# Decoupling_caps.net
KiCad netlist of a schematic drawn in Altium Designer
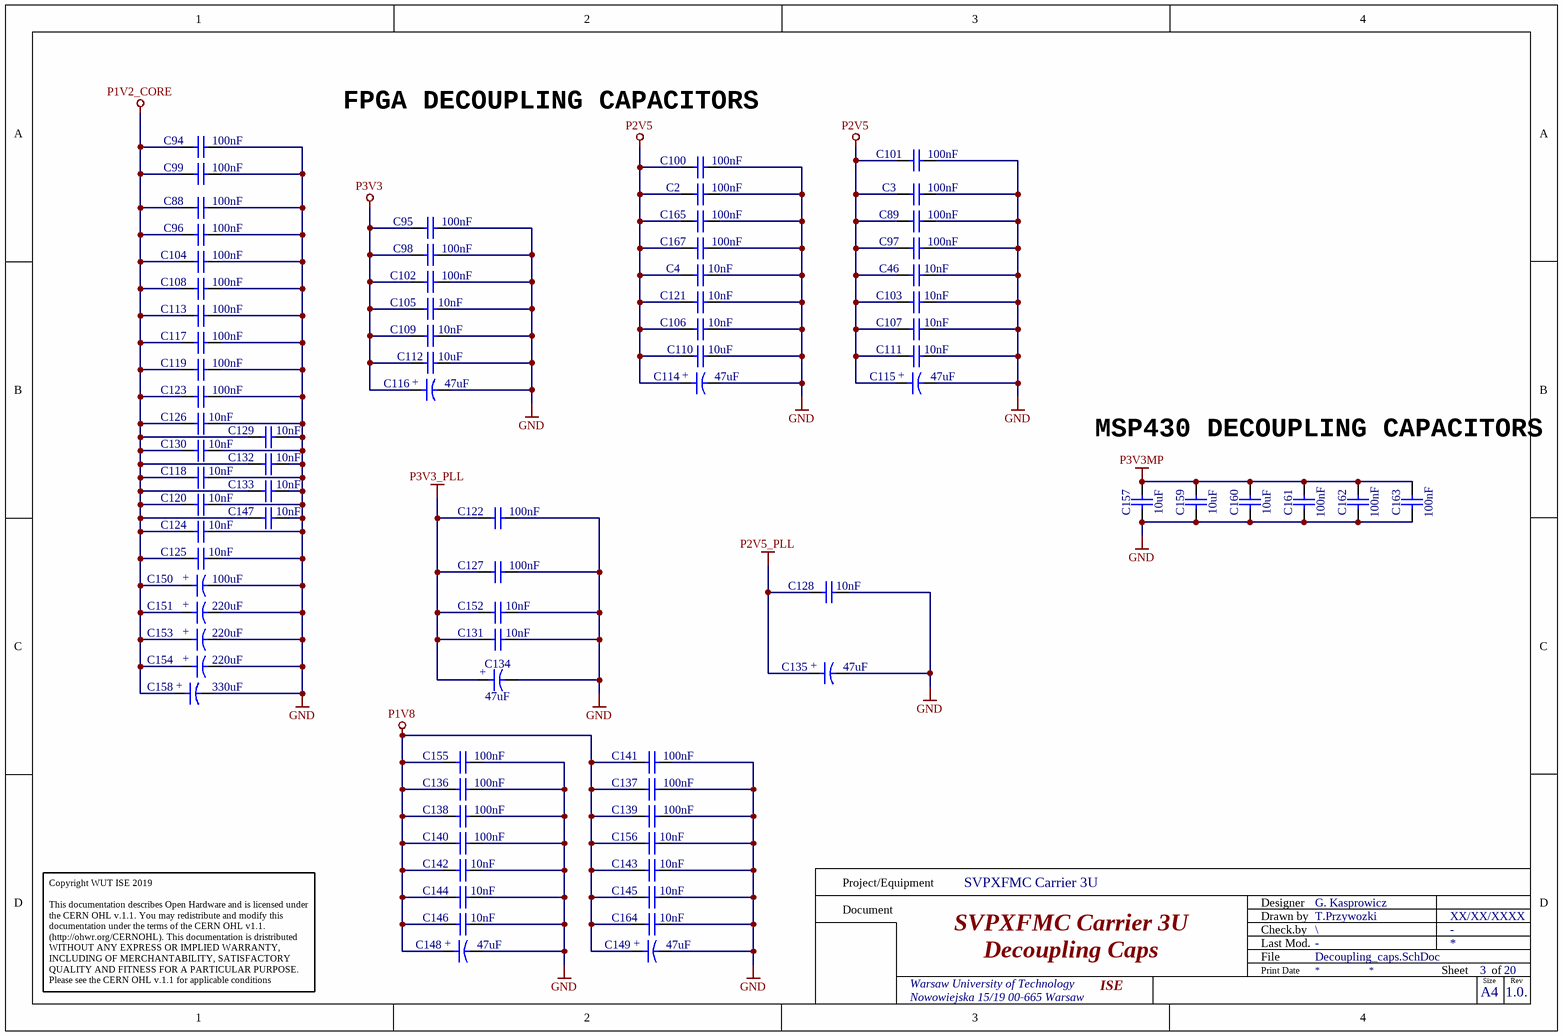
[diagram p0: Decoupling_caps.SchDoc]

(export (version "E")
  (design (tool "Eeschema 10.0.6"))
  (components
    (comp (ref "C2")
      (value "100nF")
      (footprint "CAPC0603X33N")
      (description "Non-polarised capacitor")
      (fields
        (field (name "MANUFACTURER") "GENERIC")
        (field (name "PART NUMBER") "CC0201_100NF_6.3V_10%_X5R")
        (field (name "AUTHOR") "CERN DEM JLC")
      )
      (libsource (lib "Capacitors") (part "Capacitor - non polarized"))
    )
    (comp (ref "C3")
      (value "100nF")
      (footprint "CAPC0603X33N")
      (description "Non-polarised capacitor")
      (fields
        (field (name "MANUFACTURER") "GENERIC")
        (field (name "PART NUMBER") "CC0201_100NF_6.3V_10%_X5R")
        (field (name "AUTHOR") "CERN DEM JLC")
      )
      (libsource (lib "Capacitors") (part "Capacitor - non polarized"))
    )
    (comp (ref "C4")
      (value "10nF")
      (footprint "CAPC0603X33N")
      (description "Non-polarised capacitor")
      (fields
        (field (name "MANUFACTURER") "GENERIC")
        (field (name "PART NUMBER") "CC0201_10NF_10V_10%_X5R")
        (field (name "AUTHOR") "CERN DEM JLC")
      )
      (libsource (lib "Capacitors") (part "Capacitor - non polarized"))
    )
    (comp (ref "C46")
      (value "10nF")
      (footprint "CAPC0603X33N")
      (description "Non-polarised capacitor")
      (fields
        (field (name "MANUFACTURER") "GENERIC")
        (field (name "PART NUMBER") "CC0201_10NF_10V_10%_X5R")
        (field (name "AUTHOR") "CERN DEM JLC")
      )
      (libsource (lib "Capacitors") (part "Capacitor - non polarized"))
    )
    (comp (ref "C88")
      (value "100nF")
      (footprint "CAPC0603X33N")
      (description "Non-polarised capacitor")
      (fields
        (field (name "MANUFACTURER") "GENERIC")
        (field (name "PART NUMBER") "CC0201_100NF_6.3V_10%_X5R")
        (field (name "AUTHOR") "CERN DEM JLC")
      )
      (libsource (lib "Capacitors") (part "Capacitor - non polarized"))
    )
    (comp (ref "C89")
      (value "100nF")
      (footprint "CAPC0603X33N")
      (description "Non-polarised capacitor")
      (fields
        (field (name "MANUFACTURER") "GENERIC")
        (field (name "PART NUMBER") "CC0201_100NF_6.3V_10%_X5R")
        (field (name "AUTHOR") "CERN DEM JLC")
      )
      (libsource (lib "Capacitors") (part "Capacitor - non polarized"))
    )
    (comp (ref "C94")
      (value "100nF")
      (footprint "CAPC0603X33N")
      (description "Non-polarised capacitor")
      (fields
        (field (name "MANUFACTURER") "GENERIC")
        (field (name "PART NUMBER") "CC0201_100NF_6.3V_10%_X5R")
        (field (name "AUTHOR") "CERN DEM JLC")
      )
      (libsource (lib "Capacitors") (part "Capacitor - non polarized"))
    )
    (comp (ref "C95")
      (value "100nF")
      (footprint "CAPC0603X33N")
      (description "Non-polarised capacitor")
      (fields
        (field (name "MANUFACTURER") "GENERIC")
        (field (name "PART NUMBER") "CC0201_100NF_6.3V_10%_X5R")
        (field (name "AUTHOR") "CERN DEM JLC")
      )
      (libsource (lib "Capacitors") (part "Capacitor - non polarized"))
    )
    (comp (ref "C96")
      (value "100nF")
      (footprint "CAPC0603X33N")
      (description "Non-polarised capacitor")
      (fields
        (field (name "MANUFACTURER") "GENERIC")
        (field (name "PART NUMBER") "CC0201_100NF_6.3V_10%_X5R")
        (field (name "AUTHOR") "CERN DEM JLC")
      )
      (libsource (lib "Capacitors") (part "Capacitor - non polarized"))
    )
    (comp (ref "C97")
      (value "100nF")
      (footprint "CAPC0603X33N")
      (description "Non-polarised capacitor")
      (fields
        (field (name "MANUFACTURER") "GENERIC")
        (field (name "PART NUMBER") "CC0201_100NF_6.3V_10%_X5R")
        (field (name "AUTHOR") "CERN DEM JLC")
      )
      (libsource (lib "Capacitors") (part "Capacitor - non polarized"))
    )
    (comp (ref "C98")
      (value "100nF")
      (footprint "CAPC0603X33N")
      (description "Non-polarised capacitor")
      (fields
        (field (name "MANUFACTURER") "GENERIC")
        (field (name "PART NUMBER") "CC0201_100NF_6.3V_10%_X5R")
        (field (name "AUTHOR") "CERN DEM JLC")
      )
      (libsource (lib "Capacitors") (part "Capacitor - non polarized"))
    )
    (comp (ref "C99")
      (value "100nF")
      (footprint "CAPC0603X33N")
      (description "Non-polarised capacitor")
      (fields
        (field (name "MANUFACTURER") "GENERIC")
        (field (name "PART NUMBER") "CC0201_100NF_6.3V_10%_X5R")
        (field (name "AUTHOR") "CERN DEM JLC")
      )
      (libsource (lib "Capacitors") (part "Capacitor - non polarized"))
    )
    (comp (ref "C100")
      (value "100nF")
      (footprint "CAPC0603X33N")
      (description "Non-polarised capacitor")
      (fields
        (field (name "MANUFACTURER") "GENERIC")
        (field (name "PART NUMBER") "CC0201_100NF_6.3V_10%_X5R")
        (field (name "AUTHOR") "CERN DEM JLC")
      )
      (libsource (lib "Capacitors") (part "Capacitor - non polarized"))
    )
    (comp (ref "C101")
      (value "100nF")
      (footprint "CAPC0603X33N")
      (description "Non-polarised capacitor")
      (fields
        (field (name "MANUFACTURER") "GENERIC")
        (field (name "PART NUMBER") "CC0201_100NF_6.3V_10%_X5R")
        (field (name "AUTHOR") "CERN DEM JLC")
      )
      (libsource (lib "Capacitors") (part "Capacitor - non polarized"))
    )
    (comp (ref "C102")
      (value "100nF")
      (footprint "CAPC0603X33N")
      (description "Non-polarised capacitor")
      (fields
        (field (name "MANUFACTURER") "GENERIC")
        (field (name "PART NUMBER") "CC0201_100NF_6.3V_10%_X5R")
        (field (name "AUTHOR") "CERN DEM JLC")
      )
      (libsource (lib "Capacitors") (part "Capacitor - non polarized"))
    )
    (comp (ref "C103")
      (value "10nF")
      (footprint "CAPC0603X33N")
      (description "Non-polarised capacitor")
      (fields
        (field (name "MANUFACTURER") "GENERIC")
        (field (name "PART NUMBER") "CC0201_10NF_10V_10%_X5R")
        (field (name "AUTHOR") "CERN DEM JLC")
      )
      (libsource (lib "Capacitors") (part "Capacitor - non polarized"))
    )
    (comp (ref "C104")
      (value "100nF")
      (footprint "CAPC0603X33N")
      (description "Non-polarised capacitor")
      (fields
        (field (name "MANUFACTURER") "GENERIC")
        (field (name "PART NUMBER") "CC0201_100NF_6.3V_10%_X5R")
        (field (name "AUTHOR") "CERN DEM JLC")
      )
      (libsource (lib "Capacitors") (part "Capacitor - non polarized"))
    )
    (comp (ref "C105")
      (value "10nF")
      (footprint "CAPC0603X33N")
      (description "Non-polarised capacitor")
      (fields
        (field (name "MANUFACTURER") "GENERIC")
        (field (name "PART NUMBER") "CC0201_10NF_10V_10%_X5R")
        (field (name "AUTHOR") "CERN DEM JLC")
      )
      (libsource (lib "Capacitors") (part "Capacitor - non polarized"))
    )
    (comp (ref "C106")
      (value "10nF")
      (footprint "CAPC0603X33N")
      (description "Non-polarised capacitor")
      (fields
        (field (name "MANUFACTURER") "GENERIC")
        (field (name "PART NUMBER") "CC0201_10NF_10V_10%_X5R")
        (field (name "AUTHOR") "CERN DEM JLC")
      )
      (libsource (lib "Capacitors") (part "Capacitor - non polarized"))
    )
    (comp (ref "C107")
      (value "10nF")
      (footprint "CAPC0603X33N")
      (description "Non-polarised capacitor")
      (fields
        (field (name "MANUFACTURER") "GENERIC")
        (field (name "PART NUMBER") "CC0201_10NF_10V_10%_X5R")
        (field (name "AUTHOR") "CERN DEM JLC")
      )
      (libsource (lib "Capacitors") (part "Capacitor - non polarized"))
    )
    (comp (ref "C108")
      (value "100nF")
      (footprint "CAPC0603X33N")
      (description "Non-polarised capacitor")
      (fields
        (field (name "MANUFACTURER") "GENERIC")
        (field (name "PART NUMBER") "CC0201_100NF_6.3V_10%_X5R")
        (field (name "AUTHOR") "CERN DEM JLC")
      )
      (libsource (lib "Capacitors") (part "Capacitor - non polarized"))
    )
    (comp (ref "C109")
      (value "10nF")
      (footprint "CAPC0603X33N")
      (description "Non-polarised capacitor")
      (fields
        (field (name "MANUFACTURER") "GENERIC")
        (field (name "PART NUMBER") "CC0201_10NF_10V_10%_X5R")
        (field (name "AUTHOR") "CERN DEM JLC")
      )
      (libsource (lib "Capacitors") (part "Capacitor - non polarized"))
    )
    (comp (ref "C110")
      (value "10uF")
      (footprint "CAPC2012X135N")
      (description "Non-polarised capacitor")
      (fields
        (field (name "PART NUMBER") "CC0805_10UF_16V_10%_X5R")
        (field (name "VOLTAGE") "16V")
        (field (name "AUTHOR") "CERN DEM JLC")
      )
      (libsource (lib "Capacitors") (part "Capacitor - non polarized"))
    )
    (comp (ref "C111")
      (value "10nF")
      (footprint "CAPC0603X33N")
      (description "Non-polarised capacitor")
      (fields
        (field (name "MANUFACTURER") "GENERIC")
        (field (name "PART NUMBER") "CC0201_10NF_10V_10%_X5R")
        (field (name "AUTHOR") "CERN DEM JLC")
      )
      (libsource (lib "Capacitors") (part "Capacitor - non polarized"))
    )
    (comp (ref "C112")
      (value "10uF")
      (footprint "CAPC2012X135N")
      (description "Non-polarised capacitor")
      (fields
        (field (name "PART NUMBER") "CC0805_10UF_16V_10%_X5R")
        (field (name "VOLTAGE") "16V")
        (field (name "AUTHOR") "CERN DEM JLC")
      )
      (libsource (lib "Capacitors") (part "Capacitor - non polarized"))
    )
    (comp (ref "C113")
      (value "100nF")
      (footprint "CAPC0603X33N")
      (description "Non-polarised capacitor")
      (fields
        (field (name "MANUFACTURER") "GENERIC")
        (field (name "PART NUMBER") "CC0201_100NF_6.3V_10%_X5R")
        (field (name "AUTHOR") "CERN DEM JLC")
      )
      (libsource (lib "Capacitors") (part "Capacitor - non polarized"))
    )
    (comp (ref "C114")
      (value "47uF")
      (footprint "CAPMP3528X210N")
      (description "Polarised capacitor")
      (fields
        (field (name "PART NUMBER") "CTE3528-12_47UF_10V_20%_PANASONIC_TPB")
        (field (name "VOLTAGE") "10V")
        (field (name "AUTHOR") "CERN DEM JLC")
      )
      (libsource (lib "Capacitors") (part "Capacitor - polarized"))
    )
    (comp (ref "C115")
      (value "47uF")
      (footprint "CAPMP3528X210N")
      (description "Polarised capacitor")
      (fields
        (field (name "PART NUMBER") "CTE3528-12_47UF_10V_20%_PANASONIC_TPB")
        (field (name "VOLTAGE") "10V")
        (field (name "AUTHOR") "CERN DEM JLC")
      )
      (libsource (lib "Capacitors") (part "Capacitor - polarized"))
    )
    (comp (ref "C116")
      (value "47uF")
      (footprint "CAPMP3528X210N")
      (description "Polarised capacitor")
      (fields
        (field (name "PART NUMBER") "CTE3528-12_47UF_10V_20%_PANASONIC_TPB")
        (field (name "VOLTAGE") "10V")
        (field (name "AUTHOR") "CERN DEM JLC")
      )
      (libsource (lib "Capacitors") (part "Capacitor - polarized"))
    )
    (comp (ref "C117")
      (value "100nF")
      (footprint "CAPC0603X33N")
      (description "Non-polarised capacitor")
      (fields
        (field (name "MANUFACTURER") "GENERIC")
        (field (name "PART NUMBER") "CC0201_100NF_6.3V_10%_X5R")
        (field (name "AUTHOR") "CERN DEM JLC")
      )
      (libsource (lib "Capacitors") (part "Capacitor - non polarized"))
    )
    (comp (ref "C118")
      (value "10nF")
      (footprint "CAPC0603X33N")
      (description "Non-polarised capacitor")
      (fields
        (field (name "MANUFACTURER") "GENERIC")
        (field (name "PART NUMBER") "CC0201_10NF_10V_10%_X5R")
        (field (name "AUTHOR") "CERN DEM JLC")
      )
      (libsource (lib "Capacitors") (part "Capacitor - non polarized"))
    )
    (comp (ref "C119")
      (value "100nF")
      (footprint "CAPC0603X33N")
      (description "Non-polarised capacitor")
      (fields
        (field (name "MANUFACTURER") "GENERIC")
        (field (name "PART NUMBER") "CC0201_100NF_6.3V_10%_X5R")
        (field (name "AUTHOR") "CERN DEM JLC")
      )
      (libsource (lib "Capacitors") (part "Capacitor - non polarized"))
    )
    (comp (ref "C120")
      (value "10nF")
      (footprint "CAPC0603X33N")
      (description "Non-polarised capacitor")
      (fields
        (field (name "MANUFACTURER") "GENERIC")
        (field (name "PART NUMBER") "CC0201_10NF_10V_10%_X5R")
        (field (name "AUTHOR") "CERN DEM JLC")
      )
      (libsource (lib "Capacitors") (part "Capacitor - non polarized"))
    )
    (comp (ref "C121")
      (value "10nF")
      (footprint "CAPC0603X33N")
      (description "Non-polarised capacitor")
      (fields
        (field (name "MANUFACTURER") "GENERIC")
        (field (name "PART NUMBER") "CC0201_10NF_10V_10%_X5R")
        (field (name "AUTHOR") "CERN DEM JLC")
      )
      (libsource (lib "Capacitors") (part "Capacitor - non polarized"))
    )
    (comp (ref "C122")
      (value "100nF")
      (footprint "CAPC0603X33N")
      (description "Non-polarised capacitor")
      (fields
        (field (name "MANUFACTURER") "GENERIC")
        (field (name "PART NUMBER") "CC0201_100NF_6.3V_10%_X5R")
        (field (name "AUTHOR") "CERN DEM JLC")
      )
      (libsource (lib "Capacitors") (part "Capacitor - non polarized"))
    )
    (comp (ref "C123")
      (value "100nF")
      (footprint "CAPC0603X33N")
      (description "Non-polarised capacitor")
      (fields
        (field (name "MANUFACTURER") "GENERIC")
        (field (name "PART NUMBER") "CC0201_100NF_6.3V_10%_X5R")
        (field (name "AUTHOR") "CERN DEM JLC")
      )
      (libsource (lib "Capacitors") (part "Capacitor - non polarized"))
    )
    (comp (ref "C124")
      (value "10nF")
      (footprint "CAPC0603X33N")
      (description "Non-polarised capacitor")
      (fields
        (field (name "MANUFACTURER") "GENERIC")
        (field (name "PART NUMBER") "CC0201_10NF_10V_10%_X5R")
        (field (name "AUTHOR") "CERN DEM JLC")
      )
      (libsource (lib "Capacitors") (part "Capacitor - non polarized"))
    )
    (comp (ref "C125")
      (value "10nF")
      (footprint "CAPC0603X33N")
      (description "Non-polarised capacitor")
      (fields
        (field (name "MANUFACTURER") "GENERIC")
        (field (name "PART NUMBER") "CC0201_10NF_10V_10%_X5R")
        (field (name "AUTHOR") "CERN DEM JLC")
      )
      (libsource (lib "Capacitors") (part "Capacitor - non polarized"))
    )
    (comp (ref "C126")
      (value "10nF")
      (footprint "CAPC0603X33N")
      (description "Non-polarised capacitor")
      (fields
        (field (name "MANUFACTURER") "GENERIC")
        (field (name "PART NUMBER") "CC0201_10NF_10V_10%_X5R")
        (field (name "AUTHOR") "CERN DEM JLC")
      )
      (libsource (lib "Capacitors") (part "Capacitor - non polarized"))
    )
    (comp (ref "C127")
      (value "100nF")
      (footprint "CAPC0603X33N")
      (description "Non-polarised capacitor")
      (fields
        (field (name "MANUFACTURER") "GENERIC")
        (field (name "PART NUMBER") "CC0201_100NF_6.3V_10%_X5R")
        (field (name "AUTHOR") "CERN DEM JLC")
      )
      (libsource (lib "Capacitors") (part "Capacitor - non polarized"))
    )
    (comp (ref "C128")
      (value "10nF")
      (footprint "CAPC0603X33N")
      (description "Non-polarised capacitor")
      (fields
        (field (name "MANUFACTURER") "GENERIC")
        (field (name "PART NUMBER") "CC0201_10NF_10V_10%_X5R")
        (field (name "AUTHOR") "CERN DEM JLC")
      )
      (libsource (lib "Capacitors") (part "Capacitor - non polarized"))
    )
    (comp (ref "C129")
      (value "10nF")
      (footprint "CAPC0603X33N")
      (description "Non-polarised capacitor")
      (fields
        (field (name "MANUFACTURER") "GENERIC")
        (field (name "PART NUMBER") "CC0201_10NF_10V_10%_X5R")
        (field (name "AUTHOR") "CERN DEM JLC")
      )
      (libsource (lib "Capacitors") (part "Capacitor - non polarized"))
    )
    (comp (ref "C130")
      (value "10nF")
      (footprint "CAPC0603X33N")
      (description "Non-polarised capacitor")
      (fields
        (field (name "MANUFACTURER") "GENERIC")
        (field (name "PART NUMBER") "CC0201_10NF_10V_10%_X5R")
        (field (name "AUTHOR") "CERN DEM JLC")
      )
      (libsource (lib "Capacitors") (part "Capacitor - non polarized"))
    )
    (comp (ref "C131")
      (value "10nF")
      (footprint "CAPC0603X33N")
      (description "Non-polarised capacitor")
      (fields
        (field (name "MANUFACTURER") "GENERIC")
        (field (name "PART NUMBER") "CC0201_10NF_10V_10%_X5R")
        (field (name "AUTHOR") "CERN DEM JLC")
      )
      (libsource (lib "Capacitors") (part "Capacitor - non polarized"))
    )
    (comp (ref "C132")
      (value "10nF")
      (footprint "CAPC0603X33N")
      (description "Non-polarised capacitor")
      (fields
        (field (name "MANUFACTURER") "GENERIC")
        (field (name "PART NUMBER") "CC0201_10NF_10V_10%_X5R")
        (field (name "AUTHOR") "CERN DEM JLC")
      )
      (libsource (lib "Capacitors") (part "Capacitor - non polarized"))
    )
    (comp (ref "C133")
      (value "10nF")
      (footprint "CAPC0603X33N")
      (description "Non-polarised capacitor")
      (fields
        (field (name "MANUFACTURER") "GENERIC")
        (field (name "PART NUMBER") "CC0201_10NF_10V_10%_X5R")
        (field (name "AUTHOR") "CERN DEM JLC")
      )
      (libsource (lib "Capacitors") (part "Capacitor - non polarized"))
    )
    (comp (ref "C134")
      (value "47uF")
      (footprint "CAPMP3528X210N")
      (description "Polarised capacitor")
      (fields
        (field (name "PART NUMBER") "CTE3528-12_47UF_10V_20%_PANASONIC_TPB")
        (field (name "VOLTAGE") "10V")
        (field (name "AUTHOR") "CERN DEM JLC")
      )
      (libsource (lib "Capacitors") (part "Capacitor - polarized"))
    )
    (comp (ref "C135")
      (value "47uF")
      (footprint "CAPMP3528X210N")
      (description "Polarised capacitor")
      (fields
        (field (name "PART NUMBER") "CTE3528-12_47UF_10V_20%_PANASONIC_TPB")
        (field (name "VOLTAGE") "10V")
        (field (name "AUTHOR") "CERN DEM JLC")
      )
      (libsource (lib "Capacitors") (part "Capacitor - polarized"))
    )
    (comp (ref "C136")
      (value "100nF")
      (footprint "CAPC0603X33N")
      (description "Non-polarised capacitor")
      (fields
        (field (name "MANUFACTURER") "GENERIC")
        (field (name "PART NUMBER") "CC0201_100NF_6.3V_10%_X5R")
        (field (name "AUTHOR") "CERN DEM JLC")
      )
      (libsource (lib "Capacitors") (part "Capacitor - non polarized"))
    )
    (comp (ref "C137")
      (value "100nF")
      (footprint "CAPC0603X33N")
      (description "Non-polarised capacitor")
      (fields
        (field (name "MANUFACTURER") "GENERIC")
        (field (name "PART NUMBER") "CC0201_100NF_6.3V_10%_X5R")
        (field (name "AUTHOR") "CERN DEM JLC")
      )
      (libsource (lib "Capacitors") (part "Capacitor - non polarized"))
    )
    (comp (ref "C138")
      (value "100nF")
      (footprint "CAPC0603X33N")
      (description "Non-polarised capacitor")
      (fields
        (field (name "MANUFACTURER") "GENERIC")
        (field (name "PART NUMBER") "CC0201_100NF_6.3V_10%_X5R")
        (field (name "AUTHOR") "CERN DEM JLC")
      )
      (libsource (lib "Capacitors") (part "Capacitor - non polarized"))
    )
    (comp (ref "C139")
      (value "100nF")
      (footprint "CAPC0603X33N")
      (description "Non-polarised capacitor")
      (fields
        (field (name "MANUFACTURER") "GENERIC")
        (field (name "PART NUMBER") "CC0201_100NF_6.3V_10%_X5R")
        (field (name "AUTHOR") "CERN DEM JLC")
      )
      (libsource (lib "Capacitors") (part "Capacitor - non polarized"))
    )
    (comp (ref "C140")
      (value "100nF")
      (footprint "CAPC0603X33N")
      (description "Non-polarised capacitor")
      (fields
        (field (name "MANUFACTURER") "GENERIC")
        (field (name "PART NUMBER") "CC0201_100NF_6.3V_10%_X5R")
        (field (name "AUTHOR") "CERN DEM JLC")
      )
      (libsource (lib "Capacitors") (part "Capacitor - non polarized"))
    )
    (comp (ref "C141")
      (value "100nF")
      (footprint "CAPC0603X33N")
      (description "Non-polarised capacitor")
      (fields
        (field (name "MANUFACTURER") "GENERIC")
        (field (name "PART NUMBER") "CC0201_100NF_6.3V_10%_X5R")
        (field (name "AUTHOR") "CERN DEM JLC")
      )
      (libsource (lib "Capacitors") (part "Capacitor - non polarized"))
    )
    (comp (ref "C142")
      (value "10nF")
      (footprint "CAPC0603X33N")
      (description "Non-polarised capacitor")
      (fields
        (field (name "MANUFACTURER") "GENERIC")
        (field (name "PART NUMBER") "CC0201_10NF_10V_10%_X5R")
        (field (name "AUTHOR") "CERN DEM JLC")
      )
      (libsource (lib "Capacitors") (part "Capacitor - non polarized"))
    )
    (comp (ref "C143")
      (value "10nF")
      (footprint "CAPC0603X33N")
      (description "Non-polarised capacitor")
      (fields
        (field (name "MANUFACTURER") "GENERIC")
        (field (name "PART NUMBER") "CC0201_10NF_10V_10%_X5R")
        (field (name "AUTHOR") "CERN DEM JLC")
      )
      (libsource (lib "Capacitors") (part "Capacitor - non polarized"))
    )
    (comp (ref "C144")
      (value "10nF")
      (footprint "CAPC0603X33N")
      (description "Non-polarised capacitor")
      (fields
        (field (name "MANUFACTURER") "GENERIC")
        (field (name "PART NUMBER") "CC0201_10NF_10V_10%_X5R")
        (field (name "AUTHOR") "CERN DEM JLC")
      )
      (libsource (lib "Capacitors") (part "Capacitor - non polarized"))
    )
    (comp (ref "C145")
      (value "10nF")
      (footprint "CAPC0603X33N")
      (description "Non-polarised capacitor")
      (fields
        (field (name "MANUFACTURER") "GENERIC")
        (field (name "PART NUMBER") "CC0201_10NF_10V_10%_X5R")
        (field (name "AUTHOR") "CERN DEM JLC")
      )
      (libsource (lib "Capacitors") (part "Capacitor - non polarized"))
    )
    (comp (ref "C146")
      (value "10nF")
      (footprint "CAPC0603X33N")
      (description "Non-polarised capacitor")
      (fields
        (field (name "MANUFACTURER") "GENERIC")
        (field (name "PART NUMBER") "CC0201_10NF_10V_10%_X5R")
        (field (name "AUTHOR") "CERN DEM JLC")
      )
      (libsource (lib "Capacitors") (part "Capacitor - non polarized"))
    )
    (comp (ref "C147")
      (value "10nF")
      (footprint "CAPC0603X33N")
      (description "Non-polarised capacitor")
      (fields
        (field (name "MANUFACTURER") "GENERIC")
        (field (name "PART NUMBER") "CC0201_10NF_10V_10%_X5R")
        (field (name "AUTHOR") "CERN DEM JLC")
      )
      (libsource (lib "Capacitors") (part "Capacitor - non polarized"))
    )
    (comp (ref "C148")
      (value "47uF")
      (footprint "CAPMP3528X210N")
      (description "Polarised capacitor")
      (fields
        (field (name "PART NUMBER") "CTE3528-12_47UF_10V_20%_PANASONIC_TPB")
        (field (name "VOLTAGE") "10V")
        (field (name "AUTHOR") "CERN DEM JLC")
      )
      (libsource (lib "Capacitors") (part "Capacitor - polarized"))
    )
    (comp (ref "C149")
      (value "47uF")
      (footprint "CAPMP3528X210N")
      (description "Polarised capacitor")
      (fields
        (field (name "PART NUMBER") "CTE3528-12_47UF_10V_20%_PANASONIC_TPB")
        (field (name "VOLTAGE") "10V")
        (field (name "AUTHOR") "CERN DEM JLC")
      )
      (libsource (lib "Capacitors") (part "Capacitor - polarized"))
    )
    (comp (ref "C150")
      (value "100uF")
      (footprint "CAPMP3528X210N")
      (description "Polarised capacitor")
      (fields
        (field (name "PART NUMBER") "CTE3528-21_100UF_6.3V_10%")
        (field (name "VOLTAGE") "6.3V")
        (field (name "AUTHOR") "CERN DEM JLC")
      )
      (libsource (lib "Capacitors") (part "Capacitor - polarized"))
    )
    (comp (ref "C151")
      (value "220uF")
      (footprint "CAPMP7343X310N")
      (description "Polarised capacitor")
      (fields
        (field (name "PART NUMBER") "CTE7343-31_220UF_6.3V_20%_LESR0009_KEMET_T520")
        (field (name "VOLTAGE") "6.3V")
        (field (name "AUTHOR") "CERN DEM JLC")
      )
      (libsource (lib "Capacitors") (part "Capacitor - polarized"))
    )
    (comp (ref "C152")
      (value "10nF")
      (footprint "CAPC0603X33N")
      (description "Non-polarised capacitor")
      (fields
        (field (name "MANUFACTURER") "GENERIC")
        (field (name "PART NUMBER") "CC0201_10NF_10V_10%_X5R")
        (field (name "AUTHOR") "CERN DEM JLC")
      )
      (libsource (lib "Capacitors") (part "Capacitor - non polarized"))
    )
    (comp (ref "C153")
      (value "220uF")
      (footprint "CAPMP7343X310N")
      (description "Polarised capacitor")
      (fields
        (field (name "PART NUMBER") "CTE7343-31_220UF_6.3V_20%_LESR0009_KEMET_T520")
        (field (name "VOLTAGE") "6.3V")
        (field (name "AUTHOR") "CERN DEM JLC")
      )
      (libsource (lib "Capacitors") (part "Capacitor - polarized"))
    )
    (comp (ref "C154")
      (value "220uF")
      (footprint "CAPMP7343X310N")
      (description "Polarised capacitor")
      (fields
        (field (name "PART NUMBER") "CTE7343-31_220UF_6.3V_20%_LESR0009_KEMET_T520")
        (field (name "VOLTAGE") "6.3V")
        (field (name "AUTHOR") "CERN DEM JLC")
      )
      (libsource (lib "Capacitors") (part "Capacitor - polarized"))
    )
    (comp (ref "C155")
      (value "100nF")
      (footprint "CAPC0603X33N")
      (description "Non-polarised capacitor")
      (fields
        (field (name "MANUFACTURER") "GENERIC")
        (field (name "PART NUMBER") "CC0201_100NF_6.3V_10%_X5R")
        (field (name "AUTHOR") "CERN DEM JLC")
      )
      (libsource (lib "Capacitors") (part "Capacitor - non polarized"))
    )
    (comp (ref "C156")
      (value "10nF")
      (footprint "CAPC0603X33N")
      (description "Non-polarised capacitor")
      (fields
        (field (name "MANUFACTURER") "GENERIC")
        (field (name "PART NUMBER") "CC0201_10NF_10V_10%_X5R")
        (field (name "AUTHOR") "CERN DEM JLC")
      )
      (libsource (lib "Capacitors") (part "Capacitor - non polarized"))
    )
    (comp (ref "C157")
      (value "10uF")
      (footprint "CAPC1608X80N")
      (description "Non-polarised capacitor")
      (fields
        (field (name "PART NUMBER") "CC0603_10UF_16V_20%_X5R")
        (field (name "VOLTAGE") "16V")
        (field (name "AUTHOR") "CERN DEM MR")
      )
      (libsource (lib "Capacitors") (part "Capacitor - non polarized"))
    )
    (comp (ref "C158")
      (value "330uF")
      (footprint "CAPMP7343X310N")
      (description "Polarised capacitor")
      (fields
        (field (name "MANUFACTURER") "KEMET")
        (field (name "PART NUMBER") "CTE7343-31_330UF_6.3V_20%_LESR0025_KEMET_T520")
        (field (name "AUTHOR") "CERN DEM JLC")
      )
      (libsource (lib "Capacitors") (part "Capacitor - polarized"))
    )
    (comp (ref "C159")
      (value "10uF")
      (footprint "CAPC1608X80N")
      (description "Non-polarised capacitor")
      (fields
        (field (name "PART NUMBER") "CC0603_10UF_16V_20%_X5R")
        (field (name "VOLTAGE") "16V")
        (field (name "AUTHOR") "CERN DEM MR")
      )
      (libsource (lib "Capacitors") (part "Capacitor - non polarized"))
    )
    (comp (ref "C160")
      (value "10uF")
      (footprint "CAPC1608X80N")
      (description "Non-polarised capacitor")
      (fields
        (field (name "PART NUMBER") "CC0603_10UF_16V_20%_X5R")
        (field (name "VOLTAGE") "16V")
        (field (name "AUTHOR") "CERN DEM MR")
      )
      (libsource (lib "Capacitors") (part "Capacitor - non polarized"))
    )
    (comp (ref "C161")
      (value "100nF")
      (footprint "CAPC1005X55N")
      (description "Non-polarised capacitor")
      (fields
        (field (name "PART NUMBER") "CC0402_100NF_25V_10%_X7R_YUDEN_TMK105B7104KVHF")
        (field (name "VOLTAGE") "25V")
        (field (name "AUTHOR") "CERN DEM JLC")
      )
      (libsource (lib "Capacitors") (part "Capacitor - non polarized"))
    )
    (comp (ref "C162")
      (value "100nF")
      (footprint "CAPC1005X55N")
      (description "Non-polarised capacitor")
      (fields
        (field (name "PART NUMBER") "CC0402_100NF_25V_10%_X7R_YUDEN_TMK105B7104KVHF")
        (field (name "VOLTAGE") "25V")
        (field (name "AUTHOR") "CERN DEM JLC")
      )
      (libsource (lib "Capacitors") (part "Capacitor - non polarized"))
    )
    (comp (ref "C163")
      (value "100nF")
      (footprint "CAPC1005X55N")
      (description "Non-polarised capacitor")
      (fields
        (field (name "PART NUMBER") "CC0402_100NF_25V_10%_X7R_YUDEN_TMK105B7104KVHF")
        (field (name "VOLTAGE") "25V")
        (field (name "AUTHOR") "CERN DEM JLC")
      )
      (libsource (lib "Capacitors") (part "Capacitor - non polarized"))
    )
    (comp (ref "C164")
      (value "10nF")
      (footprint "CAPC0603X33N")
      (description "Non-polarised capacitor")
      (fields
        (field (name "MANUFACTURER") "GENERIC")
        (field (name "PART NUMBER") "CC0201_10NF_10V_10%_X5R")
        (field (name "AUTHOR") "CERN DEM JLC")
      )
      (libsource (lib "Capacitors") (part "Capacitor - non polarized"))
    )
    (comp (ref "C165")
      (value "100nF")
      (footprint "CAPC0603X33N")
      (description "Non-polarised capacitor")
      (fields
        (field (name "MANUFACTURER") "GENERIC")
        (field (name "PART NUMBER") "CC0201_100NF_6.3V_10%_X5R")
        (field (name "AUTHOR") "CERN DEM JLC")
      )
      (libsource (lib "Capacitors") (part "Capacitor - non polarized"))
    )
    (comp (ref "C167")
      (value "100nF")
      (footprint "CAPC0603X33N")
      (description "Non-polarised capacitor")
      (fields
        (field (name "MANUFACTURER") "GENERIC")
        (field (name "PART NUMBER") "CC0201_100NF_6.3V_10%_X5R")
        (field (name "AUTHOR") "CERN DEM JLC")
      )
      (libsource (lib "Capacitors") (part "Capacitor - non polarized"))
    )
  )
  (nets
    (net (code "1") (name "GND") (class "Default")
      (node (ref "C100") (pin "2") (pinfunction "2_2") (pintype "passive"))
      (node (ref "C101") (pin "2") (pinfunction "2_2") (pintype "passive"))
      (node (ref "C102") (pin "2") (pinfunction "2_2") (pintype "passive"))
      (node (ref "C103") (pin "2") (pinfunction "2_2") (pintype "passive"))
      (node (ref "C104") (pin "2") (pinfunction "2_2") (pintype "passive"))
      (node (ref "C105") (pin "2") (pinfunction "2_2") (pintype "passive"))
      (node (ref "C106") (pin "2") (pinfunction "2_2") (pintype "passive"))
      (node (ref "C107") (pin "2") (pinfunction "2_2") (pintype "passive"))
      (node (ref "C108") (pin "2") (pinfunction "2_2") (pintype "passive"))
      (node (ref "C109") (pin "2") (pinfunction "2_2") (pintype "passive"))
      (node (ref "C110") (pin "2") (pinfunction "2_2") (pintype "passive"))
      (node (ref "C111") (pin "2") (pinfunction "2_2") (pintype "passive"))
      (node (ref "C112") (pin "2") (pinfunction "2_2") (pintype "passive"))
      (node (ref "C113") (pin "2") (pinfunction "2_2") (pintype "passive"))
      (node (ref "C114") (pin "2") (pinfunction "2_2") (pintype "passive"))
      (node (ref "C115") (pin "2") (pinfunction "2_2") (pintype "passive"))
      (node (ref "C116") (pin "2") (pinfunction "2_2") (pintype "passive"))
      (node (ref "C117") (pin "2") (pinfunction "2_2") (pintype "passive"))
      (node (ref "C118") (pin "2") (pinfunction "2_2") (pintype "passive"))
      (node (ref "C119") (pin "2") (pinfunction "2_2") (pintype "passive"))
      (node (ref "C120") (pin "2") (pinfunction "2_2") (pintype "passive"))
      (node (ref "C121") (pin "2") (pinfunction "2_2") (pintype "passive"))
      (node (ref "C122") (pin "2") (pinfunction "2_2") (pintype "passive"))
      (node (ref "C123") (pin "2") (pinfunction "2_2") (pintype "passive"))
      (node (ref "C124") (pin "2") (pinfunction "2_2") (pintype "passive"))
      (node (ref "C125") (pin "2") (pinfunction "2_2") (pintype "passive"))
      (node (ref "C126") (pin "2") (pinfunction "2_2") (pintype "passive"))
      (node (ref "C127") (pin "2") (pinfunction "2_2") (pintype "passive"))
      (node (ref "C128") (pin "2") (pinfunction "2_2") (pintype "passive"))
      (node (ref "C129") (pin "2") (pinfunction "2_2") (pintype "passive"))
      (node (ref "C130") (pin "2") (pinfunction "2_2") (pintype "passive"))
      (node (ref "C131") (pin "2") (pinfunction "2_2") (pintype "passive"))
      (node (ref "C132") (pin "2") (pinfunction "2_2") (pintype "passive"))
      (node (ref "C133") (pin "2") (pinfunction "2_2") (pintype "passive"))
      (node (ref "C134") (pin "2") (pinfunction "2_2") (pintype "passive"))
      (node (ref "C135") (pin "2") (pinfunction "2_2") (pintype "passive"))
      (node (ref "C136") (pin "2") (pinfunction "2_2") (pintype "passive"))
      (node (ref "C137") (pin "2") (pinfunction "2_2") (pintype "passive"))
      (node (ref "C138") (pin "2") (pinfunction "2_2") (pintype "passive"))
      (node (ref "C139") (pin "2") (pinfunction "2_2") (pintype "passive"))
      (node (ref "C140") (pin "2") (pinfunction "2_2") (pintype "passive"))
      (node (ref "C141") (pin "2") (pinfunction "2_2") (pintype "passive"))
      (node (ref "C142") (pin "2") (pinfunction "2_2") (pintype "passive"))
      (node (ref "C143") (pin "2") (pinfunction "2_2") (pintype "passive"))
      (node (ref "C144") (pin "2") (pinfunction "2_2") (pintype "passive"))
      (node (ref "C145") (pin "2") (pinfunction "2_2") (pintype "passive"))
      (node (ref "C146") (pin "2") (pinfunction "2_2") (pintype "passive"))
      (node (ref "C147") (pin "2") (pinfunction "2_2") (pintype "passive"))
      (node (ref "C148") (pin "2") (pinfunction "2_2") (pintype "passive"))
      (node (ref "C149") (pin "2") (pinfunction "2_2") (pintype "passive"))
      (node (ref "C150") (pin "2") (pinfunction "2_2") (pintype "passive"))
      (node (ref "C151") (pin "2") (pinfunction "2_2") (pintype "passive"))
      (node (ref "C152") (pin "2") (pinfunction "2_2") (pintype "passive"))
      (node (ref "C153") (pin "2") (pinfunction "2_2") (pintype "passive"))
      (node (ref "C154") (pin "2") (pinfunction "2_2") (pintype "passive"))
      (node (ref "C155") (pin "2") (pinfunction "2_2") (pintype "passive"))
      (node (ref "C156") (pin "2") (pinfunction "2_2") (pintype "passive"))
      (node (ref "C157") (pin "1") (pinfunction "1_1") (pintype "passive"))
      (node (ref "C158") (pin "2") (pinfunction "2_2") (pintype "passive"))
      (node (ref "C159") (pin "1") (pinfunction "1_1") (pintype "passive"))
      (node (ref "C160") (pin "1") (pinfunction "1_1") (pintype "passive"))
      (node (ref "C161") (pin "1") (pinfunction "1_1") (pintype "passive"))
      (node (ref "C162") (pin "1") (pinfunction "1_1") (pintype "passive"))
      (node (ref "C163") (pin "1") (pinfunction "1_1") (pintype "passive"))
      (node (ref "C164") (pin "2") (pinfunction "2_2") (pintype "passive"))
      (node (ref "C165") (pin "2") (pinfunction "2_2") (pintype "passive"))
      (node (ref "C167") (pin "2") (pinfunction "2_2") (pintype "passive"))
      (node (ref "C2") (pin "2") (pinfunction "2_2") (pintype "passive"))
      (node (ref "C3") (pin "2") (pinfunction "2_2") (pintype "passive"))
      (node (ref "C4") (pin "2") (pinfunction "2_2") (pintype "passive"))
      (node (ref "C46") (pin "2") (pinfunction "2_2") (pintype "passive"))
      (node (ref "C88") (pin "2") (pinfunction "2_2") (pintype "passive"))
      (node (ref "C89") (pin "2") (pinfunction "2_2") (pintype "passive"))
      (node (ref "C94") (pin "2") (pinfunction "2_2") (pintype "passive"))
      (node (ref "C95") (pin "2") (pinfunction "2_2") (pintype "passive"))
      (node (ref "C96") (pin "2") (pinfunction "2_2") (pintype "passive"))
      (node (ref "C97") (pin "2") (pinfunction "2_2") (pintype "passive"))
      (node (ref "C98") (pin "2") (pinfunction "2_2") (pintype "passive"))
      (node (ref "C99") (pin "2") (pinfunction "2_2") (pintype "passive"))
    )
    (net (code "2") (name "P1V2_CORE") (class "Default")
      (node (ref "C104") (pin "1") (pinfunction "1_1") (pintype "passive"))
      (node (ref "C108") (pin "1") (pinfunction "1_1") (pintype "passive"))
      (node (ref "C113") (pin "1") (pinfunction "1_1") (pintype "passive"))
      (node (ref "C117") (pin "1") (pinfunction "1_1") (pintype "passive"))
      (node (ref "C118") (pin "1") (pinfunction "1_1") (pintype "passive"))
      (node (ref "C119") (pin "1") (pinfunction "1_1") (pintype "passive"))
      (node (ref "C120") (pin "1") (pinfunction "1_1") (pintype "passive"))
      (node (ref "C123") (pin "1") (pinfunction "1_1") (pintype "passive"))
      (node (ref "C124") (pin "1") (pinfunction "1_1") (pintype "passive"))
      (node (ref "C125") (pin "1") (pinfunction "1_1") (pintype "passive"))
      (node (ref "C126") (pin "1") (pinfunction "1_1") (pintype "passive"))
      (node (ref "C129") (pin "1") (pinfunction "1_1") (pintype "passive"))
      (node (ref "C130") (pin "1") (pinfunction "1_1") (pintype "passive"))
      (node (ref "C132") (pin "1") (pinfunction "1_1") (pintype "passive"))
      (node (ref "C133") (pin "1") (pinfunction "1_1") (pintype "passive"))
      (node (ref "C147") (pin "1") (pinfunction "1_1") (pintype "passive"))
      (node (ref "C150") (pin "1") (pinfunction "1_1") (pintype "passive"))
      (node (ref "C151") (pin "1") (pinfunction "1_1") (pintype "passive"))
      (node (ref "C153") (pin "1") (pinfunction "1_1") (pintype "passive"))
      (node (ref "C154") (pin "1") (pinfunction "1_1") (pintype "passive"))
      (node (ref "C158") (pin "1") (pinfunction "1_1") (pintype "passive"))
      (node (ref "C88") (pin "1") (pinfunction "1_1") (pintype "passive"))
      (node (ref "C94") (pin "1") (pinfunction "1_1") (pintype "passive"))
      (node (ref "C96") (pin "1") (pinfunction "1_1") (pintype "passive"))
      (node (ref "C99") (pin "1") (pinfunction "1_1") (pintype "passive"))
    )
    (net (code "3") (name "P1V8") (class "Default")
      (node (ref "C136") (pin "1") (pinfunction "1_1") (pintype "passive"))
      (node (ref "C137") (pin "1") (pinfunction "1_1") (pintype "passive"))
      (node (ref "C138") (pin "1") (pinfunction "1_1") (pintype "passive"))
      (node (ref "C139") (pin "1") (pinfunction "1_1") (pintype "passive"))
      (node (ref "C140") (pin "1") (pinfunction "1_1") (pintype "passive"))
      (node (ref "C141") (pin "1") (pinfunction "1_1") (pintype "passive"))
      (node (ref "C142") (pin "1") (pinfunction "1_1") (pintype "passive"))
      (node (ref "C143") (pin "1") (pinfunction "1_1") (pintype "passive"))
      (node (ref "C144") (pin "1") (pinfunction "1_1") (pintype "passive"))
      (node (ref "C145") (pin "1") (pinfunction "1_1") (pintype "passive"))
      (node (ref "C146") (pin "1") (pinfunction "1_1") (pintype "passive"))
      (node (ref "C148") (pin "1") (pinfunction "1_1") (pintype "passive"))
      (node (ref "C149") (pin "1") (pinfunction "1_1") (pintype "passive"))
      (node (ref "C155") (pin "1") (pinfunction "1_1") (pintype "passive"))
      (node (ref "C156") (pin "1") (pinfunction "1_1") (pintype "passive"))
      (node (ref "C164") (pin "1") (pinfunction "1_1") (pintype "passive"))
    )
    (net (code "4") (name "P2V5") (class "Default")
      (node (ref "C100") (pin "1") (pinfunction "1_1") (pintype "passive"))
      (node (ref "C101") (pin "1") (pinfunction "1_1") (pintype "passive"))
      (node (ref "C103") (pin "1") (pinfunction "1_1") (pintype "passive"))
      (node (ref "C106") (pin "1") (pinfunction "1_1") (pintype "passive"))
      (node (ref "C107") (pin "1") (pinfunction "1_1") (pintype "passive"))
      (node (ref "C110") (pin "1") (pinfunction "1_1") (pintype "passive"))
      (node (ref "C111") (pin "1") (pinfunction "1_1") (pintype "passive"))
      (node (ref "C114") (pin "1") (pinfunction "1_1") (pintype "passive"))
      (node (ref "C115") (pin "1") (pinfunction "1_1") (pintype "passive"))
      (node (ref "C121") (pin "1") (pinfunction "1_1") (pintype "passive"))
      (node (ref "C165") (pin "1") (pinfunction "1_1") (pintype "passive"))
      (node (ref "C167") (pin "1") (pinfunction "1_1") (pintype "passive"))
      (node (ref "C2") (pin "1") (pinfunction "1_1") (pintype "passive"))
      (node (ref "C3") (pin "1") (pinfunction "1_1") (pintype "passive"))
      (node (ref "C4") (pin "1") (pinfunction "1_1") (pintype "passive"))
      (node (ref "C46") (pin "1") (pinfunction "1_1") (pintype "passive"))
      (node (ref "C89") (pin "1") (pinfunction "1_1") (pintype "passive"))
      (node (ref "C97") (pin "1") (pinfunction "1_1") (pintype "passive"))
    )
    (net (code "5") (name "P2V5_PLL") (class "Default")
      (node (ref "C128") (pin "1") (pinfunction "1_1") (pintype "passive"))
      (node (ref "C135") (pin "1") (pinfunction "1_1") (pintype "passive"))
    )
    (net (code "6") (name "P3V3") (class "Default")
      (node (ref "C102") (pin "1") (pinfunction "1_1") (pintype "passive"))
      (node (ref "C105") (pin "1") (pinfunction "1_1") (pintype "passive"))
      (node (ref "C109") (pin "1") (pinfunction "1_1") (pintype "passive"))
      (node (ref "C112") (pin "1") (pinfunction "1_1") (pintype "passive"))
      (node (ref "C116") (pin "1") (pinfunction "1_1") (pintype "passive"))
      (node (ref "C95") (pin "1") (pinfunction "1_1") (pintype "passive"))
      (node (ref "C98") (pin "1") (pinfunction "1_1") (pintype "passive"))
    )
    (net (code "7") (name "P3V3MP") (class "Default")
      (node (ref "C157") (pin "2") (pinfunction "2_2") (pintype "passive"))
      (node (ref "C159") (pin "2") (pinfunction "2_2") (pintype "passive"))
      (node (ref "C160") (pin "2") (pinfunction "2_2") (pintype "passive"))
      (node (ref "C161") (pin "2") (pinfunction "2_2") (pintype "passive"))
      (node (ref "C162") (pin "2") (pinfunction "2_2") (pintype "passive"))
      (node (ref "C163") (pin "2") (pinfunction "2_2") (pintype "passive"))
    )
    (net (code "8") (name "P3V3_PLL") (class "Default")
      (node (ref "C122") (pin "1") (pinfunction "1_1") (pintype "passive"))
      (node (ref "C127") (pin "1") (pinfunction "1_1") (pintype "passive"))
      (node (ref "C131") (pin "1") (pinfunction "1_1") (pintype "passive"))
      (node (ref "C134") (pin "1") (pinfunction "1_1") (pintype "passive"))
      (node (ref "C152") (pin "1") (pinfunction "1_1") (pintype "passive"))
    )
  )
)
